# PWR2.net
KiCad netlist of a schematic drawn in Altium Designer
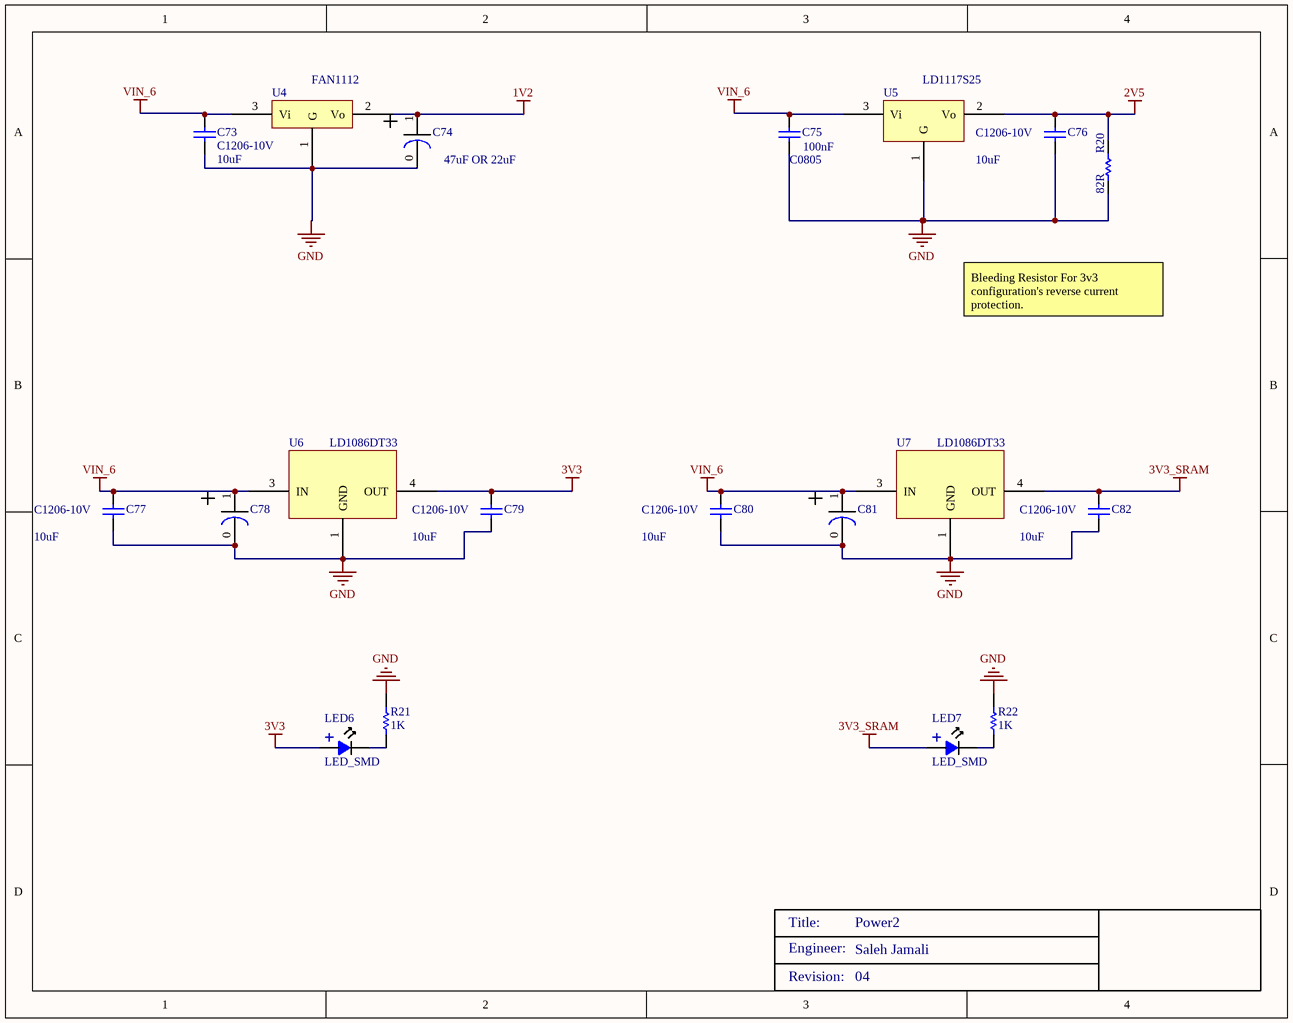
[diagram p0: PWR2.SchDoc]

(export (version "E")
  (design (tool "Eeschema 10.0.6"))
  (components
    (comp (ref "C73")
      (value "C1206-10V")
      (footprint "1206")
      (description "Ceramic Chip Capacitor - Standard")
      (fields (field (name "ALTIUM_VALUE") "10uF") (field (name "PUBLISHER") "Altium Limited"))
      (libsource (lib "KEMET Chip Capacitor") (part "C1206"))
    )
    (comp (ref "C74")
      (value "47uF OR 22uF")
      (footprint "22_47u_10A")
      (libsource (lib "SMD_ELECTRLT_CAP") (part "Electrolytic SMD Cap"))
    )
    (comp (ref "C75")
      (value "C0805")
      (footprint "0805")
      (description "Ceramic Chip Capacitor - Standard")
      (fields (field (name "ALTIUM_VALUE") "100nF") (field (name "PUBLISHER") "Altium Limited"))
      (libsource (lib "KEMET Chip Capacitor") (part "C0805"))
    )
    (comp (ref "C76")
      (value "C1206-10V")
      (footprint "1206")
      (description "Ceramic Chip Capacitor - Standard")
      (fields (field (name "ALTIUM_VALUE") "10uF") (field (name "PUBLISHER") "Altium Limited"))
      (libsource (lib "KEMET Chip Capacitor") (part "C1206"))
    )
    (comp (ref "C77")
      (value "C1206-10V")
      (footprint "1206")
      (description "Ceramic Chip Capacitor - Standard")
      (fields (field (name "ALTIUM_VALUE") "10uF") (field (name "PUBLISHER") "Altium Limited"))
      (libsource (lib "KEMET Chip Capacitor") (part "C1206"))
    )
    (comp (ref "C78")
      (value "Electrolytic SMD Cap")
      (footprint "22_47u_10A")
      (libsource (lib "SMD_ELECTRLT_CAP") (part "Electrolytic SMD Cap"))
    )
    (comp (ref "C79")
      (value "C1206-10V")
      (footprint "1206")
      (description "Ceramic Chip Capacitor - Standard")
      (fields (field (name "ALTIUM_VALUE") "10uF") (field (name "PUBLISHER") "Altium Limited"))
      (libsource (lib "KEMET Chip Capacitor") (part "C1206"))
    )
    (comp (ref "C80")
      (value "C1206-10V")
      (footprint "1206")
      (description "Ceramic Chip Capacitor - Standard")
      (fields (field (name "ALTIUM_VALUE") "10uF") (field (name "PUBLISHER") "Altium Limited"))
      (libsource (lib "KEMET Chip Capacitor") (part "C1206"))
    )
    (comp (ref "C81")
      (value "Electrolytic SMD Cap")
      (footprint "22_47u_10A")
      (libsource (lib "SMD_ELECTRLT_CAP") (part "Electrolytic SMD Cap"))
    )
    (comp (ref "C82")
      (value "C1206-10V")
      (footprint "1206")
      (description "Ceramic Chip Capacitor - Standard")
      (fields (field (name "ALTIUM_VALUE") "10uF") (field (name "PUBLISHER") "Altium Limited"))
      (libsource (lib "KEMET Chip Capacitor") (part "C1206"))
    )
    (comp (ref "LED6") (value "LED_SMD") (footprint "LED_805") (libsource (lib "LED_PRJCT") (part "LED_SMD")))
    (comp (ref "LED7") (value "LED_SMD") (footprint "LED_805") (libsource (lib "LED_PRJCT") (part "LED_SMD")))
    (comp (ref "R20")
      (value "82R")
      (footprint "ERA-0805")
      (fields (field (name "PUBLISHER") "Altium Limited"))
      (libsource (lib "Panasonic Resistor") (part "ERA6Y"))
    )
    (comp (ref "R21")
      (value "1K")
      (footprint "ERA-0805")
      (fields (field (name "PUBLISHER") "Altium Limited"))
      (libsource (lib "Panasonic Resistor") (part "ERA6Y"))
    )
    (comp (ref "R22")
      (value "1K")
      (footprint "ERA-0805")
      (fields (field (name "PUBLISHER") "Altium Limited"))
      (libsource (lib "Panasonic Resistor") (part "ERA6Y"))
    )
    (comp (ref "U4")
      (value "FAN1112")
      (footprint "DPAK_TO252")
      (description "1.2 volt regulator")
      (libsource (lib "FAN1112_DPAK") (part "FAN1112_1.2V_REGULATER"))
    )
    (comp (ref "U5")
      (value "LD1117S25")
      (footprint "SOT223")
      (description "2.5 volt, 800mA Regulator")
      (libsource (lib "LD1117S25_SOT223") (part "LD1117S25"))
    )
    (comp (ref "U6")
      (value "LD1086DT33")
      (footprint "LD1086DT33")
      (description "LOW DROP FIXED AND ADJUSTABLE  POSITIVE VOLTAGE REGULATORS")
      (libsource (lib "LD1086DT33_PRJCT") (part "LD1086DT33"))
    )
    (comp (ref "U7")
      (value "LD1086DT33")
      (footprint "LD1086DT33")
      (description "LOW DROP FIXED AND ADJUSTABLE  POSITIVE VOLTAGE REGULATORS")
      (libsource (lib "LD1086DT33_PRJCT") (part "LD1086DT33"))
    )
  )
  (nets
    (net (code "1") (name "1V2") (class "Default")
      (node (ref "C74") (pin "1") (pinfunction "1_1") (pintype "passive"))
      (node (ref "U4") (pin "2") (pinfunction "Vo_2") (pintype "power_in"))
    )
    (net (code "2") (name "2V5") (class "Default")
      (node (ref "C76") (pin "1") (pinfunction "1_1") (pintype "passive"))
      (node (ref "R20") (pin "2") (pinfunction "2_2") (pintype "passive"))
      (node (ref "U5") (pin "2") (pinfunction "Vo_2") (pintype "power_in"))
    )
    (net (code "3") (name "3V3") (class "Default")
      (node (ref "C79") (pin "1") (pinfunction "1_1") (pintype "passive"))
      (node (ref "LED6") (pin "1") (pinfunction "1_1") (pintype "passive"))
      (node (ref "U6") (pin "4") (pinfunction "OUT_4") (pintype "passive"))
    )
    (net (code "4") (name "3V3_SRAM") (class "Default")
      (node (ref "C82") (pin "1") (pinfunction "1_1") (pintype "passive"))
      (node (ref "LED7") (pin "1") (pinfunction "1_1") (pintype "passive"))
      (node (ref "U7") (pin "4") (pinfunction "OUT_4") (pintype "passive"))
    )
    (net (code "5") (name "GND") (class "Default")
      (node (ref "C73") (pin "2") (pinfunction "2_2") (pintype "passive"))
      (node (ref "C74") (pin "0") (pinfunction "0_0") (pintype "passive"))
      (node (ref "C75") (pin "2") (pinfunction "2_2") (pintype "passive"))
      (node (ref "C76") (pin "2") (pinfunction "2_2") (pintype "passive"))
      (node (ref "C77") (pin "2") (pinfunction "2_2") (pintype "passive"))
      (node (ref "C78") (pin "0") (pinfunction "0_0") (pintype "passive"))
      (node (ref "C79") (pin "2") (pinfunction "2_2") (pintype "passive"))
      (node (ref "C80") (pin "2") (pinfunction "2_2") (pintype "passive"))
      (node (ref "C81") (pin "0") (pinfunction "0_0") (pintype "passive"))
      (node (ref "C82") (pin "2") (pinfunction "2_2") (pintype "passive"))
      (node (ref "R20") (pin "1") (pinfunction "1_1") (pintype "passive"))
      (node (ref "R21") (pin "1") (pinfunction "1_1") (pintype "passive"))
      (node (ref "R22") (pin "1") (pinfunction "1_1") (pintype "passive"))
      (node (ref "U4") (pin "1") (pinfunction "G_1") (pintype "power_in"))
      (node (ref "U5") (pin "1") (pinfunction "G_1") (pintype "power_in"))
      (node (ref "U6") (pin "1") (pinfunction "GND_1") (pintype "passive"))
      (node (ref "U7") (pin "1") (pinfunction "GND_1") (pintype "passive"))
    )
    (net (code "6") (name "Net-(LED6-Pad2)") (class "Default")
      (node (ref "LED6") (pin "2") (pinfunction "2_2") (pintype "passive"))
      (node (ref "R21") (pin "2") (pinfunction "2_2") (pintype "passive"))
    )
    (net (code "7") (name "Net-(LED7-Pad2)") (class "Default")
      (node (ref "LED7") (pin "2") (pinfunction "2_2") (pintype "passive"))
      (node (ref "R22") (pin "2") (pinfunction "2_2") (pintype "passive"))
    )
    (net (code "8") (name "VIN_6") (class "Default")
      (node (ref "C73") (pin "1") (pinfunction "1_1") (pintype "passive"))
      (node (ref "C75") (pin "1") (pinfunction "1_1") (pintype "passive"))
      (node (ref "C77") (pin "1") (pinfunction "1_1") (pintype "passive"))
      (node (ref "C78") (pin "1") (pinfunction "1_1") (pintype "passive"))
      (node (ref "C80") (pin "1") (pinfunction "1_1") (pintype "passive"))
      (node (ref "C81") (pin "1") (pinfunction "1_1") (pintype "passive"))
      (node (ref "U4") (pin "3") (pinfunction "Vi_3") (pintype "power_in"))
      (node (ref "U5") (pin "3") (pinfunction "Vi_3") (pintype "power_in"))
      (node (ref "U6") (pin "3") (pinfunction "IN_3") (pintype "passive"))
      (node (ref "U7") (pin "3") (pinfunction "IN_3") (pintype "passive"))
    )
  )
)
